# T1200.net
KiCad netlist of a schematic drawn in EAGLE
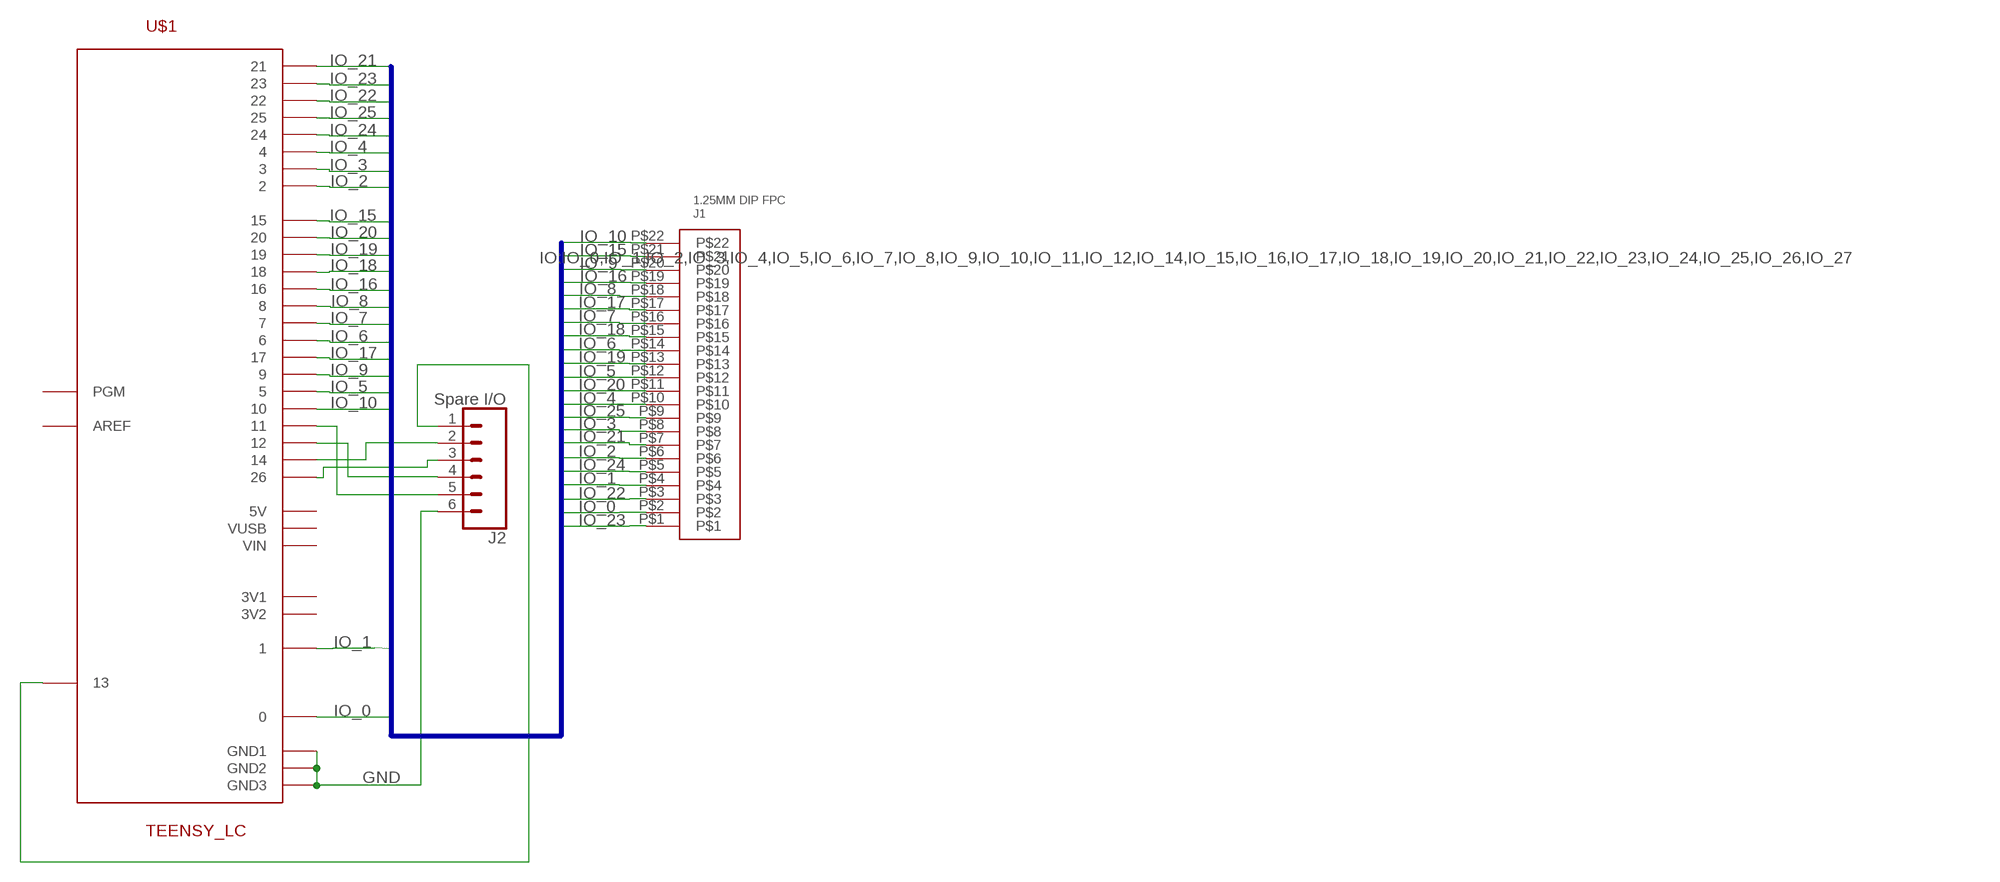
[diagram p0: schematic, sheet 1]

(export (version "E")
  (design (tool "Eeschema 10.0.6"))
  (components
    (comp (ref "J1")
      (value "1.25MM DIP FPC")
      (footprint "eagle-import:T1200_CON")
      (libsource (lib "eagle-import") (part "T1200_CON"))
    )
    (comp (ref "J2")
      (value "Spare I/O")
      (footprint "eagle-import:1X06")
      (libsource (lib "eagle-import") (part "CONN_06SILK_FEMALE_PTH"))
    )
    (comp (ref "U$1")
      (value "TEENSY_LC")
      (footprint "eagle-import:TEENSY_LC")
      (libsource (lib "eagle-import") (part "TEENSY_LC"))
    )
  )
  (nets
    (net (code "7") (name "/GND") (class "Default")
      (node (ref "J2") (pin "6") (pinfunction "6_6") (pintype "passive"))
      (node (ref "U$1") (pin "GND1") (pinfunction "GND1_GND1") (pintype "bidirectional"))
      (node (ref "U$1") (pin "GND2") (pinfunction "GND2_GND2") (pintype "bidirectional"))
      (node (ref "U$1") (pin "GND3") (pinfunction "GND3_GND3") (pintype "bidirectional"))
    )
    (net (code "8") (name "/IO_0") (class "Default")
      (node (ref "J1") (pin "P$2") (pinfunction "P$2_P$2") (pintype "bidirectional"))
      (node (ref "U$1") (pin "0") (pinfunction "0_0") (pintype "bidirectional"))
    )
    (net (code "9") (name "/IO_1") (class "Default")
      (node (ref "J1") (pin "P$4") (pinfunction "P$4_P$4") (pintype "bidirectional"))
      (node (ref "U$1") (pin "1") (pinfunction "1_1") (pintype "bidirectional"))
    )
    (net (code "10") (name "/IO_2") (class "Default")
      (node (ref "J1") (pin "P$6") (pinfunction "P$6_P$6") (pintype "bidirectional"))
      (node (ref "U$1") (pin "2") (pinfunction "2_2") (pintype "bidirectional"))
    )
    (net (code "11") (name "/IO_3") (class "Default")
      (node (ref "J1") (pin "P$8") (pinfunction "P$8_P$8") (pintype "bidirectional"))
      (node (ref "U$1") (pin "3") (pinfunction "3_3") (pintype "bidirectional"))
    )
    (net (code "12") (name "/IO_4") (class "Default")
      (node (ref "J1") (pin "P$10") (pinfunction "P$10_P$10") (pintype "bidirectional"))
      (node (ref "U$1") (pin "4") (pinfunction "4_4") (pintype "bidirectional"))
    )
    (net (code "13") (name "/IO_5") (class "Default")
      (node (ref "J1") (pin "P$12") (pinfunction "P$12_P$12") (pintype "bidirectional"))
      (node (ref "U$1") (pin "5") (pinfunction "5_5") (pintype "bidirectional"))
    )
    (net (code "14") (name "/IO_6") (class "Default")
      (node (ref "J1") (pin "P$14") (pinfunction "P$14_P$14") (pintype "bidirectional"))
      (node (ref "U$1") (pin "6") (pinfunction "6_6") (pintype "bidirectional"))
    )
    (net (code "15") (name "/IO_7") (class "Default")
      (node (ref "J1") (pin "P$16") (pinfunction "P$16_P$16") (pintype "bidirectional"))
      (node (ref "U$1") (pin "7") (pinfunction "7_7") (pintype "bidirectional"))
    )
    (net (code "16") (name "/IO_8") (class "Default")
      (node (ref "J1") (pin "P$18") (pinfunction "P$18_P$18") (pintype "bidirectional"))
      (node (ref "U$1") (pin "8") (pinfunction "8_8") (pintype "bidirectional"))
    )
    (net (code "17") (name "/IO_9") (class "Default")
      (node (ref "J1") (pin "P$20") (pinfunction "P$20_P$20") (pintype "bidirectional"))
      (node (ref "U$1") (pin "9") (pinfunction "9_9") (pintype "bidirectional"))
    )
    (net (code "18") (name "/IO_10") (class "Default")
      (node (ref "J1") (pin "P$22") (pinfunction "P$22_P$22") (pintype "bidirectional"))
      (node (ref "U$1") (pin "10") (pinfunction "10_10") (pintype "bidirectional"))
    )
    (net (code "19") (name "/IO_15") (class "Default")
      (node (ref "J1") (pin "P$21") (pinfunction "P$21_P$21") (pintype "bidirectional"))
      (node (ref "U$1") (pin "15") (pinfunction "15_15") (pintype "bidirectional"))
    )
    (net (code "20") (name "/IO_16") (class "Default")
      (node (ref "J1") (pin "P$19") (pinfunction "P$19_P$19") (pintype "bidirectional"))
      (node (ref "U$1") (pin "16") (pinfunction "16_16") (pintype "bidirectional"))
    )
    (net (code "21") (name "/IO_17") (class "Default")
      (node (ref "J1") (pin "P$17") (pinfunction "P$17_P$17") (pintype "bidirectional"))
      (node (ref "U$1") (pin "17") (pinfunction "17_17") (pintype "bidirectional"))
    )
    (net (code "22") (name "/IO_18") (class "Default")
      (node (ref "J1") (pin "P$15") (pinfunction "P$15_P$15") (pintype "bidirectional"))
      (node (ref "U$1") (pin "18") (pinfunction "18_18") (pintype "bidirectional"))
    )
    (net (code "23") (name "/IO_19") (class "Default")
      (node (ref "J1") (pin "P$13") (pinfunction "P$13_P$13") (pintype "bidirectional"))
      (node (ref "U$1") (pin "19") (pinfunction "19_19") (pintype "bidirectional"))
    )
    (net (code "24") (name "/IO_20") (class "Default")
      (node (ref "J1") (pin "P$11") (pinfunction "P$11_P$11") (pintype "bidirectional"))
      (node (ref "U$1") (pin "20") (pinfunction "20_20") (pintype "bidirectional"))
    )
    (net (code "25") (name "/IO_21") (class "Default")
      (node (ref "J1") (pin "P$7") (pinfunction "P$7_P$7") (pintype "bidirectional"))
      (node (ref "U$1") (pin "21") (pinfunction "21_21") (pintype "bidirectional"))
    )
    (net (code "26") (name "/IO_22") (class "Default")
      (node (ref "J1") (pin "P$3") (pinfunction "P$3_P$3") (pintype "bidirectional"))
      (node (ref "U$1") (pin "22") (pinfunction "22_22") (pintype "bidirectional"))
    )
    (net (code "27") (name "/IO_23") (class "Default")
      (node (ref "J1") (pin "P$1") (pinfunction "P$1_P$1") (pintype "bidirectional"))
      (node (ref "U$1") (pin "23") (pinfunction "23_23") (pintype "bidirectional"))
    )
    (net (code "28") (name "/IO_24") (class "Default")
      (node (ref "J1") (pin "P$5") (pinfunction "P$5_P$5") (pintype "bidirectional"))
      (node (ref "U$1") (pin "24") (pinfunction "24_24") (pintype "bidirectional"))
    )
    (net (code "29") (name "/IO_25") (class "Default")
      (node (ref "J1") (pin "P$9") (pinfunction "P$9_P$9") (pintype "bidirectional"))
      (node (ref "U$1") (pin "25") (pinfunction "25_25") (pintype "bidirectional"))
    )
    (net (code "31") (name "Net-(J2-Pad1)") (class "Default")
      (node (ref "J2") (pin "1") (pinfunction "1_1") (pintype "passive"))
      (node (ref "U$1") (pin "13") (pinfunction "13_13") (pintype "bidirectional"))
    )
    (net (code "32") (name "Net-(J2-Pad2)") (class "Default")
      (node (ref "J2") (pin "2") (pinfunction "2_2") (pintype "passive"))
      (node (ref "U$1") (pin "14") (pinfunction "14_14") (pintype "bidirectional"))
    )
    (net (code "33") (name "Net-(J2-Pad3)") (class "Default")
      (node (ref "J2") (pin "3") (pinfunction "3_3") (pintype "passive"))
      (node (ref "U$1") (pin "26") (pinfunction "26_26") (pintype "bidirectional"))
    )
    (net (code "34") (name "Net-(J2-Pad4)") (class "Default")
      (node (ref "J2") (pin "4") (pinfunction "4_4") (pintype "passive"))
      (node (ref "U$1") (pin "12") (pinfunction "12_12") (pintype "bidirectional"))
    )
    (net (code "35") (name "Net-(J2-Pad5)") (class "Default")
      (node (ref "J2") (pin "5") (pinfunction "5_5") (pintype "passive"))
      (node (ref "U$1") (pin "11") (pinfunction "11_11") (pintype "bidirectional"))
    )
    (net (code "36") (name "unconnected-(U$1-Pad3V1)") (class "Default")
      (node (ref "U$1") (pin "3V1") (pinfunction "3V1_3V1") (pintype "bidirectional"))
    )
    (net (code "37") (name "unconnected-(U$1-Pad3V2)") (class "Default")
      (node (ref "U$1") (pin "3V2") (pinfunction "3V2_3V2") (pintype "bidirectional"))
    )
    (net (code "38") (name "unconnected-(U$1-Pad5V)") (class "Default")
      (node (ref "U$1") (pin "5V") (pinfunction "5V_5V") (pintype "bidirectional"))
    )
    (net (code "39") (name "unconnected-(U$1-PadAREF)") (class "Default")
      (node (ref "U$1") (pin "AREF") (pinfunction "AREF_AREF") (pintype "bidirectional"))
    )
    (net (code "40") (name "unconnected-(U$1-PadPGM)") (class "Default")
      (node (ref "U$1") (pin "PGM") (pinfunction "PGM_PGM") (pintype "bidirectional"))
    )
    (net (code "41") (name "unconnected-(U$1-PadVIN)") (class "Default")
      (node (ref "U$1") (pin "VIN") (pinfunction "VIN_VIN") (pintype "bidirectional"))
    )
    (net (code "42") (name "unconnected-(U$1-PadVUSB)") (class "Default")
      (node (ref "U$1") (pin "VUSB") (pinfunction "VUSB_VUSB") (pintype "bidirectional"))
    )
  )
)
